# W-BT.net
KiCad netlist of a schematic drawn in EAGLE
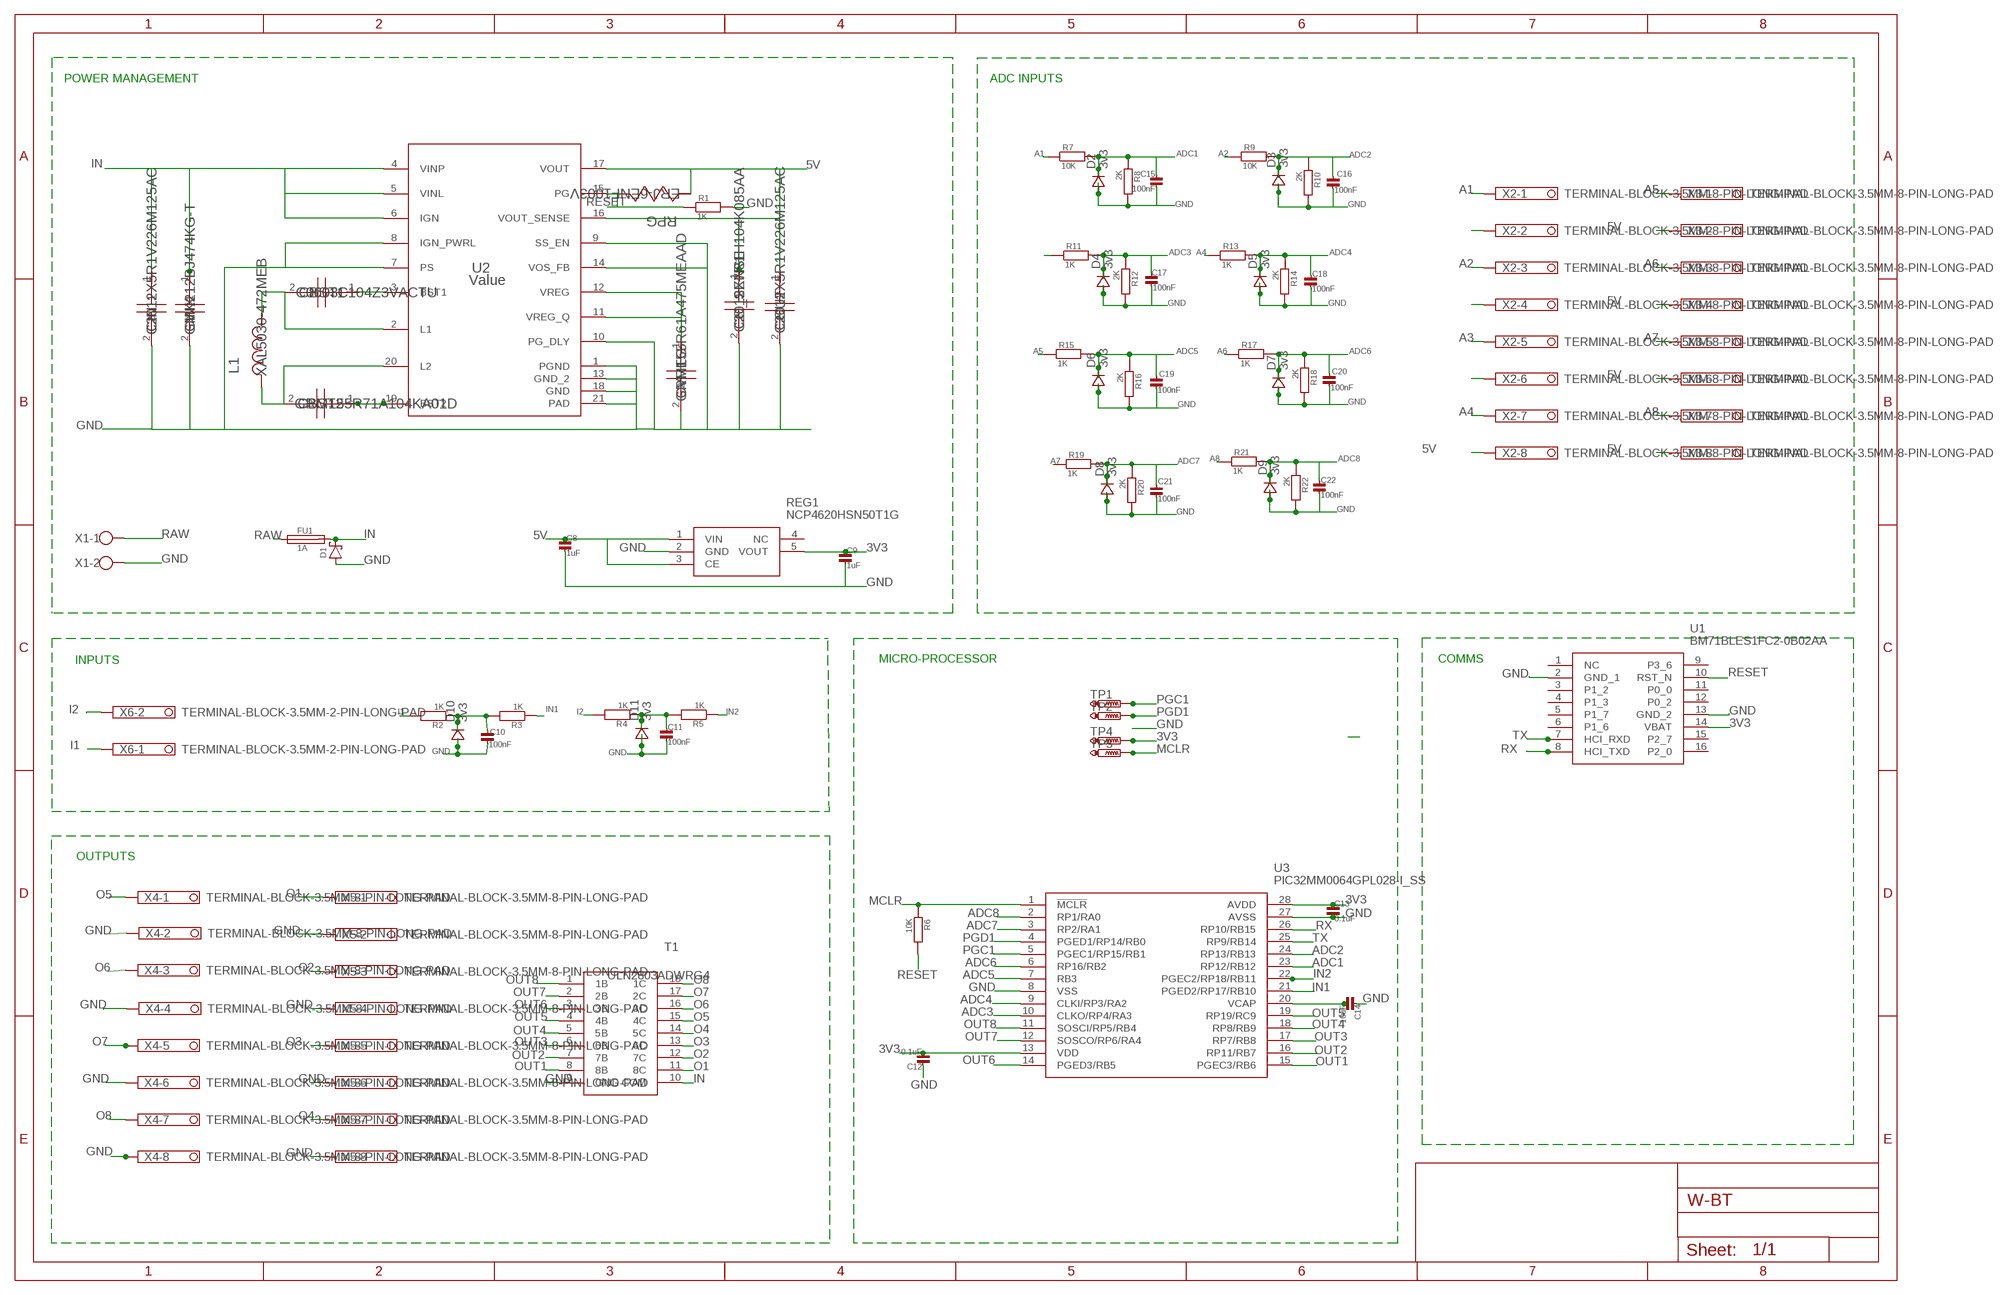
[diagram p0: schematic, sheet 1]

(export (version "E")
  (design (tool "Eeschema 10.0.6"))
  (components
    (comp (ref "C8")
      (value "1uF")
      (footprint "eagle-import:C0402")
      (libsource (lib "eagle-import") (part "CC0402"))
    )
    (comp (ref "C9")
      (value "1uF")
      (footprint "eagle-import:C0402")
      (libsource (lib "eagle-import") (part "CC0402"))
    )
    (comp (ref "C10")
      (value "100nF")
      (footprint "eagle-import:C0402")
      (libsource (lib "eagle-import") (part "CC0402"))
    )
    (comp (ref "C11")
      (value "100nF")
      (footprint "eagle-import:C0402")
      (libsource (lib "eagle-import") (part "CC0402"))
    )
    (comp (ref "C12")
      (value "0.1uF")
      (footprint "eagle-import:C0402")
      (libsource (lib "eagle-import") (part "CC0402"))
    )
    (comp (ref "C13")
      (value "0.1uF")
      (footprint "eagle-import:C0402")
      (libsource (lib "eagle-import") (part "CC0402"))
    )
    (comp (ref "C14")
      (value "10uF")
      (footprint "eagle-import:C0402")
      (libsource (lib "eagle-import") (part "CC0402"))
    )
    (comp (ref "C15")
      (value "100nF")
      (footprint "eagle-import:C0402")
      (libsource (lib "eagle-import") (part "CC0402"))
    )
    (comp (ref "C16")
      (value "100nF")
      (footprint "eagle-import:C0402")
      (libsource (lib "eagle-import") (part "CC0402"))
    )
    (comp (ref "C17")
      (value "100nF")
      (footprint "eagle-import:C0402")
      (libsource (lib "eagle-import") (part "CC0402"))
    )
    (comp (ref "C18")
      (value "100nF")
      (footprint "eagle-import:C0402")
      (libsource (lib "eagle-import") (part "CC0402"))
    )
    (comp (ref "C19")
      (value "100nF")
      (footprint "eagle-import:C0402")
      (libsource (lib "eagle-import") (part "CC0402"))
    )
    (comp (ref "C20")
      (value "100nF")
      (footprint "eagle-import:C0402")
      (libsource (lib "eagle-import") (part "CC0402"))
    )
    (comp (ref "C21")
      (value "100nF")
      (footprint "eagle-import:C0402")
      (libsource (lib "eagle-import") (part "CC0402"))
    )
    (comp (ref "C22")
      (value "100nF")
      (footprint "eagle-import:C0402")
      (libsource (lib "eagle-import") (part "CC0402"))
    )
    (comp (ref "CBST1")
      (value "C0603C104Z3VACTU")
      (footprint "eagle-import:0603")
      (libsource (lib "eagle-import") (part "C0603C104Z3VACTU"))
    )
    (comp (ref "CBST2")
      (value "GRM155R71A104KA01D")
      (footprint "eagle-import:0402")
      (libsource (lib "eagle-import") (part "GRM155R71A104KA01D"))
    )
    (comp (ref "CIN")
      (value "C2012X5R1V226M125AC")
      (footprint "eagle-import:0805")
      (libsource (lib "eagle-import") (part "C2012X5R1V226M125AC"))
    )
    (comp (ref "CINX")
      (value "GMK212BJ474KG-T")
      (footprint "eagle-import:0805")
      (fields (field (name "MANUFACTURER_PART_NUMBER") "GMK212BJ474KGT"))
      (libsource (lib "eagle-import") (part "GMK212BJ474KG-T"))
    )
    (comp (ref "COUT")
      (value "C2012X5R1V226M125AC")
      (footprint "eagle-import:0805")
      (libsource (lib "eagle-import") (part "C2012X5R1V226M125AC"))
    )
    (comp (ref "CO_SENSE")
      (value "C2012X7R1H104K085AA")
      (footprint "eagle-import:0805")
      (libsource (lib "eagle-import") (part "C2012X7R1H104K085AA"))
    )
    (comp (ref "CVREG")
      (value "GRM155R61A475MEAAD")
      (footprint "eagle-import:0402")
      (libsource (lib "eagle-import") (part "GRM155R61A475MEAAD"))
    )
    (comp (ref "D1")
      (value "SCHOTTKY-DIODESMD")
      (footprint "eagle-import:SMB")
      (libsource (lib "eagle-import") (part "SCHOTTKY-DIODESMD"))
    )
    (comp (ref "D2")
      (value "3v3")
      (footprint "eagle-import:SOD323")
      (fields (field (name "MPN") "CDSOD323-T05C"))
      (libsource (lib "eagle-import") (part "DSOD323"))
    )
    (comp (ref "D3")
      (value "3v3")
      (footprint "eagle-import:SOD323")
      (fields (field (name "MPN") "CDSOD323-T05C"))
      (libsource (lib "eagle-import") (part "DSOD323"))
    )
    (comp (ref "D4")
      (value "3v3")
      (footprint "eagle-import:SOD323")
      (fields (field (name "MPN") "CDSOD323-T05C"))
      (libsource (lib "eagle-import") (part "DSOD323"))
    )
    (comp (ref "D5")
      (value "3v3")
      (footprint "eagle-import:SOD323")
      (fields (field (name "MPN") "CDSOD323-T05C"))
      (libsource (lib "eagle-import") (part "DSOD323"))
    )
    (comp (ref "D6")
      (value "3v3")
      (footprint "eagle-import:SOD323")
      (fields (field (name "MPN") "CDSOD323-T05C"))
      (libsource (lib "eagle-import") (part "DSOD323"))
    )
    (comp (ref "D7")
      (value "3v3")
      (footprint "eagle-import:SOD323")
      (fields (field (name "MPN") "CDSOD323-T05C"))
      (libsource (lib "eagle-import") (part "DSOD323"))
    )
    (comp (ref "D8")
      (value "3v3")
      (footprint "eagle-import:SOD323")
      (fields (field (name "MPN") "CDSOD323-T05C"))
      (libsource (lib "eagle-import") (part "DSOD323"))
    )
    (comp (ref "D9")
      (value "3v3")
      (footprint "eagle-import:SOD323")
      (fields (field (name "MPN") "CDSOD323-T05C"))
      (libsource (lib "eagle-import") (part "DSOD323"))
    )
    (comp (ref "D10")
      (value "3v3")
      (footprint "eagle-import:SOD323")
      (fields (field (name "MPN") "CDSOD323-T05C"))
      (libsource (lib "eagle-import") (part "DSOD323"))
    )
    (comp (ref "D11")
      (value "3v3")
      (footprint "eagle-import:SOD323")
      (fields (field (name "MPN") "CDSOD323-T05C"))
      (libsource (lib "eagle-import") (part "DSOD323"))
    )
    (comp (ref "FU1")
      (value "1A")
      (footprint "eagle-import:MF-SMDF050")
      (libsource (lib "eagle-import") (part "MF-SMDF050"))
    )
    (comp (ref "L1")
      (value "XAL5030-472MEB")
      (footprint "eagle-import:XAL5030")
      (fields (field (name "MANUFACTURER_PART_NUMBER") "XAL5030472MEB"))
      (libsource (lib "eagle-import") (part "XAL5030-472MEB"))
    )
    (comp (ref "R1")
      (value "1K")
      (footprint "eagle-import:R0402")
      (libsource (lib "eagle-import") (part "RR0402"))
    )
    (comp (ref "R2")
      (value "1K")
      (footprint "eagle-import:R0402")
      (libsource (lib "eagle-import") (part "RR0402"))
    )
    (comp (ref "R3")
      (value "1K")
      (footprint "eagle-import:R0402")
      (libsource (lib "eagle-import") (part "RR0402"))
    )
    (comp (ref "R4")
      (value "1K")
      (footprint "eagle-import:R0402")
      (libsource (lib "eagle-import") (part "RR0402"))
    )
    (comp (ref "R5")
      (value "1K")
      (footprint "eagle-import:R0402")
      (libsource (lib "eagle-import") (part "RR0402"))
    )
    (comp (ref "R6")
      (value "10K")
      (footprint "eagle-import:R0402")
      (libsource (lib "eagle-import") (part "RR0402"))
    )
    (comp (ref "R7")
      (value "10K")
      (footprint "eagle-import:R0402")
      (libsource (lib "eagle-import") (part "RR0402"))
    )
    (comp (ref "R8")
      (value "2K")
      (footprint "eagle-import:R0402")
      (libsource (lib "eagle-import") (part "RR0402"))
    )
    (comp (ref "R9")
      (value "10K")
      (footprint "eagle-import:R0402")
      (libsource (lib "eagle-import") (part "RR0402"))
    )
    (comp (ref "R10")
      (value "2K")
      (footprint "eagle-import:R0402")
      (libsource (lib "eagle-import") (part "RR0402"))
    )
    (comp (ref "R11")
      (value "1K")
      (footprint "eagle-import:R0402")
      (libsource (lib "eagle-import") (part "RR0402"))
    )
    (comp (ref "R12")
      (value "2K")
      (footprint "eagle-import:R0402")
      (libsource (lib "eagle-import") (part "RR0402"))
    )
    (comp (ref "R13")
      (value "1K")
      (footprint "eagle-import:R0402")
      (libsource (lib "eagle-import") (part "RR0402"))
    )
    (comp (ref "R14")
      (value "2K")
      (footprint "eagle-import:R0402")
      (libsource (lib "eagle-import") (part "RR0402"))
    )
    (comp (ref "R15")
      (value "1K")
      (footprint "eagle-import:R0402")
      (libsource (lib "eagle-import") (part "RR0402"))
    )
    (comp (ref "R16")
      (value "2K")
      (footprint "eagle-import:R0402")
      (libsource (lib "eagle-import") (part "RR0402"))
    )
    (comp (ref "R17")
      (value "1K")
      (footprint "eagle-import:R0402")
      (libsource (lib "eagle-import") (part "RR0402"))
    )
    (comp (ref "R18")
      (value "2K")
      (footprint "eagle-import:R0402")
      (libsource (lib "eagle-import") (part "RR0402"))
    )
    (comp (ref "R19")
      (value "1K")
      (footprint "eagle-import:R0402")
      (libsource (lib "eagle-import") (part "RR0402"))
    )
    (comp (ref "R20")
      (value "2K")
      (footprint "eagle-import:R0402")
      (libsource (lib "eagle-import") (part "RR0402"))
    )
    (comp (ref "R21")
      (value "1K")
      (footprint "eagle-import:R0402")
      (libsource (lib "eagle-import") (part "RR0402"))
    )
    (comp (ref "R22")
      (value "2K")
      (footprint "eagle-import:R0402")
      (libsource (lib "eagle-import") (part "RR0402"))
    )
    (comp (ref "REG1")
      (value "NCP4620HSN50T1G")
      (footprint "eagle-import:SOT95P280X145-5N")
      (fields
        (field (name "MOUSER_PART_NUMBER") "863-NCP4620HSN50T1G")
        (field (name "RS_PART_NUMBER") "7484802")
      )
      (libsource (lib "eagle-import") (part "NCP4620HSN50T1G"))
    )
    (comp (ref "RPG")
      (value "ERJ-6ENF1003V")
      (footprint "eagle-import:0805")
      (fields
        (field (name "MANUFACTURER_PART_NUMBER") "ERJ6ENF1003V")
        (field (name "POWER") "0.125")
        (field (name "TOLERANCE") "1.0")
      )
      (libsource (lib "eagle-import") (part "ERJ-6ENF1003V"))
    )
    (comp (ref "T1")
      (value "ULN2803ADWRG4")
      (footprint "eagle-import:SOIC127P1030X265-18N")
      (fields (field (name "MOUSER_PART_NUMBER") "595-ULN2803ADWRG4"))
      (libsource (lib "eagle-import") (part "ULN2803ADWRG4"))
    )
    (comp (ref "TP1")
      (value "PTR1TP13R")
      (footprint "eagle-import:TP13R")
      (libsource (lib "eagle-import") (part "PTR1TP13R"))
    )
    (comp (ref "TP2")
      (value "PTR1TP13R")
      (footprint "eagle-import:TP13R")
      (libsource (lib "eagle-import") (part "PTR1TP13R"))
    )
    (comp (ref "TP4")
      (value "PTR1TP13R")
      (footprint "eagle-import:TP13R")
      (libsource (lib "eagle-import") (part "PTR1TP13R"))
    )
    (comp (ref "TP5")
      (value "PTR1TP13SQ")
      (footprint "eagle-import:TP13SQ")
      (libsource (lib "eagle-import") (part "PTR1TP13SQ"))
    )
    (comp (ref "U1")
      (value "BM71BLES1FC2-0B02AA")
      (footprint "eagle-import:BM71BLES1FC2_1")
      (fields
        (field (name "MOUSER_PART_NUMBER") "579-71BLES1FC20B02AA")
        (field (name "RS_PART_NUMBER") "1717856P")
      )
      (libsource (lib "eagle-import") (part "BM71BLES1FC2-0B02AA"))
    )
    (comp (ref "U2")
      (value "Value")
      (footprint "eagle-import:PWP0020P_N")
      (fields
        (field (name "MANUFACTURER") "Texas Instruments")
        (field (name "MANUFACTURER_PART_NUMBER") "TPS55165QPWPRQ1")
        (field (name "PARTNUMBER") "TPS55165PWPQ1")
      )
      (libsource (lib "eagle-import") (part "TPS55165QPWPRQ1"))
    )
    (comp (ref "U3")
      (value "PIC32MM0064GPL028-I_SS")
      (footprint "eagle-import:SOP65P780X200-28N")
      (fields
        (field (name "MANUFACTURER_PART_NUMBER") "PIC32MM0064GPL028-I/SS")
        (field (name "MOUSER_PART_NUMBER") "579-2MM0064GPL028ISS")
        (field (name "RS_PART_NUMBER") "1463267")
      )
      (libsource (lib "eagle-import") (part "PIC32MM0064GPL028-I_SS"))
    )
    (comp (ref "X1")
      (value "W237-102")
      (footprint "eagle-import:W237-102")
      (fields (field (name "MPN") "237-102"))
      (libsource (lib "eagle-import") (part "W237-102"))
    )
    (comp (ref "X2")
      (value "TERMINAL-BLOCK-3.5MM-8-PIN-LONG-PAD")
      (footprint "eagle-import:TERMINAL-BLOCK-8-PIN-3.5MM-LONG-PAD")
      (libsource (lib "eagle-import") (part "TERMINAL-BLOCK-3.5MM-8-PIN-LONG-PAD"))
    )
    (comp (ref "X3")
      (value "TERMINAL-BLOCK-3.5MM-8-PIN-LONG-PAD")
      (footprint "eagle-import:TERMINAL-BLOCK-8-PIN-3.5MM-LONG-PAD")
      (libsource (lib "eagle-import") (part "TERMINAL-BLOCK-3.5MM-8-PIN-LONG-PAD"))
    )
    (comp (ref "X4")
      (value "TERMINAL-BLOCK-3.5MM-8-PIN-LONG-PAD")
      (footprint "eagle-import:TERMINAL-BLOCK-8-PIN-3.5MM-LONG-PAD")
      (libsource (lib "eagle-import") (part "TERMINAL-BLOCK-3.5MM-8-PIN-LONG-PAD"))
    )
    (comp (ref "X5")
      (value "TERMINAL-BLOCK-3.5MM-8-PIN-LONG-PAD")
      (footprint "eagle-import:TERMINAL-BLOCK-8-PIN-3.5MM-LONG-PAD")
      (libsource (lib "eagle-import") (part "TERMINAL-BLOCK-3.5MM-8-PIN-LONG-PAD"))
    )
    (comp (ref "X6")
      (value "TERMINAL-BLOCK-3.5MM-2-PIN-LONG-PAD")
      (footprint "eagle-import:TERMINAL-BLOCK-2-PIN-3.5MM-LONG-PAD")
      (libsource (lib "eagle-import") (part "TERMINAL-BLOCK-3.5MM-2-PIN-LONG-PAD"))
    )
  )
  (nets
    (net (code "1") (name "/3V3") (class "Default")
      (node (ref "C12") (pin "2") (pinfunction "2_2") (pintype "passive"))
      (node (ref "C13") (pin "1") (pinfunction "1_1") (pintype "passive"))
      (node (ref "C9") (pin "1") (pinfunction "1_1") (pintype "passive"))
      (node (ref "REG1") (pin "5") (pinfunction "VOUT_5") (pintype "output"))
      (node (ref "TP4") (pin "TP") (pinfunction "TP_TP") (pintype "input"))
      (node (ref "U1") (pin "14") (pinfunction "VBAT_14") (pintype "bidirectional"))
      (node (ref "U3") (pin "13") (pinfunction "VDD_13") (pintype "bidirectional"))
      (node (ref "U3") (pin "28") (pinfunction "AVDD_28") (pintype "bidirectional"))
    )
    (net (code "2") (name "/5V") (class "Default")
      (node (ref "C8") (pin "1") (pinfunction "1_1") (pintype "passive"))
      (node (ref "COUT") (pin "1") (pinfunction "1_1") (pintype "passive"))
      (node (ref "CO_SENSE") (pin "1") (pinfunction "1_1") (pintype "passive"))
      (node (ref "REG1") (pin "1") (pinfunction "VIN_1") (pintype "input"))
      (node (ref "REG1") (pin "3") (pinfunction "CE_3") (pintype "bidirectional"))
      (node (ref "RPG") (pin "2") (pinfunction "2_2") (pintype "passive"))
      (node (ref "U2") (pin "16") (pinfunction "VOUT_SENSE_16") (pintype "input"))
      (node (ref "U2") (pin "17") (pinfunction "VOUT_17") (pintype "power_in"))
      (node (ref "X2") (pin "2") (pinfunction "K_2") (pintype "passive"))
      (node (ref "X2") (pin "4") (pinfunction "K_4") (pintype "passive"))
      (node (ref "X2") (pin "6") (pinfunction "K_6") (pintype "passive"))
      (node (ref "X2") (pin "8") (pinfunction "K_8") (pintype "passive"))
      (node (ref "X3") (pin "2") (pinfunction "K_2") (pintype "passive"))
      (node (ref "X3") (pin "4") (pinfunction "K_4") (pintype "passive"))
      (node (ref "X3") (pin "6") (pinfunction "K_6") (pintype "passive"))
      (node (ref "X3") (pin "8") (pinfunction "K_8") (pintype "passive"))
    )
    (net (code "3") (name "/A1") (class "Default")
      (node (ref "R7") (pin "1") (pinfunction "1_1") (pintype "passive"))
      (node (ref "X2") (pin "1") (pinfunction "K_1") (pintype "passive"))
    )
    (net (code "4") (name "/A2") (class "Default")
      (node (ref "R9") (pin "1") (pinfunction "1_1") (pintype "passive"))
      (node (ref "X2") (pin "3") (pinfunction "K_3") (pintype "passive"))
    )
    (net (code "5") (name "/A3") (class "Default")
      (node (ref "R11") (pin "1") (pinfunction "1_1") (pintype "passive"))
      (node (ref "X2") (pin "5") (pinfunction "K_5") (pintype "passive"))
    )
    (net (code "6") (name "/A4") (class "Default")
      (node (ref "R13") (pin "1") (pinfunction "1_1") (pintype "passive"))
      (node (ref "X2") (pin "7") (pinfunction "K_7") (pintype "passive"))
    )
    (net (code "7") (name "/A5") (class "Default")
      (node (ref "R15") (pin "1") (pinfunction "1_1") (pintype "passive"))
      (node (ref "X3") (pin "1") (pinfunction "K_1") (pintype "passive"))
    )
    (net (code "8") (name "/A6") (class "Default")
      (node (ref "R17") (pin "1") (pinfunction "1_1") (pintype "passive"))
      (node (ref "X3") (pin "3") (pinfunction "K_3") (pintype "passive"))
    )
    (net (code "9") (name "/A7") (class "Default")
      (node (ref "R19") (pin "1") (pinfunction "1_1") (pintype "passive"))
      (node (ref "X3") (pin "5") (pinfunction "K_5") (pintype "passive"))
    )
    (net (code "10") (name "/A8") (class "Default")
      (node (ref "R21") (pin "1") (pinfunction "1_1") (pintype "passive"))
      (node (ref "X3") (pin "7") (pinfunction "K_7") (pintype "passive"))
    )
    (net (code "11") (name "/ADC1") (class "Default")
      (node (ref "C15") (pin "1") (pinfunction "1_1") (pintype "passive"))
      (node (ref "D2") (pin "1") (pinfunction "C_1") (pintype "passive"))
      (node (ref "R7") (pin "2") (pinfunction "2_2") (pintype "passive"))
      (node (ref "R8") (pin "1") (pinfunction "1_1") (pintype "passive"))
      (node (ref "U3") (pin "23") (pinfunction "RP12/RB12_23") (pintype "bidirectional"))
    )
    (net (code "12") (name "/ADC2") (class "Default")
      (node (ref "C16") (pin "1") (pinfunction "1_1") (pintype "passive"))
      (node (ref "D3") (pin "1") (pinfunction "C_1") (pintype "passive"))
      (node (ref "R10") (pin "1") (pinfunction "1_1") (pintype "passive"))
      (node (ref "R9") (pin "2") (pinfunction "2_2") (pintype "passive"))
      (node (ref "U3") (pin "24") (pinfunction "RP13/RB13_24") (pintype "bidirectional"))
    )
    (net (code "13") (name "/ADC3") (class "Default")
      (node (ref "C17") (pin "1") (pinfunction "1_1") (pintype "passive"))
      (node (ref "D4") (pin "1") (pinfunction "C_1") (pintype "passive"))
      (node (ref "R11") (pin "2") (pinfunction "2_2") (pintype "passive"))
      (node (ref "R12") (pin "1") (pinfunction "1_1") (pintype "passive"))
      (node (ref "U3") (pin "10") (pinfunction "CLKO/RP4/RA3_10") (pintype "bidirectional"))
    )
    (net (code "14") (name "/ADC4") (class "Default")
      (node (ref "C18") (pin "1") (pinfunction "1_1") (pintype "passive"))
      (node (ref "D5") (pin "1") (pinfunction "C_1") (pintype "passive"))
      (node (ref "R13") (pin "2") (pinfunction "2_2") (pintype "passive"))
      (node (ref "R14") (pin "1") (pinfunction "1_1") (pintype "passive"))
      (node (ref "U3") (pin "9") (pinfunction "CLKI/RP3/RA2_9") (pintype "bidirectional"))
    )
    (net (code "15") (name "/ADC5") (class "Default")
      (node (ref "C19") (pin "1") (pinfunction "1_1") (pintype "passive"))
      (node (ref "D6") (pin "1") (pinfunction "C_1") (pintype "passive"))
      (node (ref "R15") (pin "2") (pinfunction "2_2") (pintype "passive"))
      (node (ref "R16") (pin "1") (pinfunction "1_1") (pintype "passive"))
      (node (ref "U3") (pin "7") (pinfunction "RB3_7") (pintype "bidirectional"))
    )
    (net (code "16") (name "/ADC6") (class "Default")
      (node (ref "C20") (pin "1") (pinfunction "1_1") (pintype "passive"))
      (node (ref "D7") (pin "1") (pinfunction "C_1") (pintype "passive"))
      (node (ref "R17") (pin "2") (pinfunction "2_2") (pintype "passive"))
      (node (ref "R18") (pin "1") (pinfunction "1_1") (pintype "passive"))
      (node (ref "U3") (pin "6") (pinfunction "RP16/RB2_6") (pintype "bidirectional"))
    )
    (net (code "17") (name "/ADC7") (class "Default")
      (node (ref "C21") (pin "1") (pinfunction "1_1") (pintype "passive"))
      (node (ref "D8") (pin "1") (pinfunction "C_1") (pintype "passive"))
      (node (ref "R19") (pin "2") (pinfunction "2_2") (pintype "passive"))
      (node (ref "R20") (pin "1") (pinfunction "1_1") (pintype "passive"))
      (node (ref "U3") (pin "3") (pinfunction "RP2/RA1_3") (pintype "bidirectional"))
    )
    (net (code "18") (name "/ADC8") (class "Default")
      (node (ref "C22") (pin "1") (pinfunction "1_1") (pintype "passive"))
      (node (ref "D9") (pin "1") (pinfunction "C_1") (pintype "passive"))
      (node (ref "R21") (pin "2") (pinfunction "2_2") (pintype "passive"))
      (node (ref "R22") (pin "1") (pinfunction "1_1") (pintype "passive"))
      (node (ref "U3") (pin "2") (pinfunction "RP1/RA0_2") (pintype "bidirectional"))
    )
    (net (code "19") (name "/GND") (class "Default")
      (node (ref "C10") (pin "2") (pinfunction "2_2") (pintype "passive"))
      (node (ref "C11") (pin "2") (pinfunction "2_2") (pintype "passive"))
      (node (ref "C12") (pin "1") (pinfunction "1_1") (pintype "passive"))
      (node (ref "C13") (pin "2") (pinfunction "2_2") (pintype "passive"))
      (node (ref "C14") (pin "1") (pinfunction "1_1") (pintype "passive"))
      (node (ref "C15") (pin "2") (pinfunction "2_2") (pintype "passive"))
      (node (ref "C16") (pin "2") (pinfunction "2_2") (pintype "passive"))
      (node (ref "C17") (pin "2") (pinfunction "2_2") (pintype "passive"))
      (node (ref "C18") (pin "2") (pinfunction "2_2") (pintype "passive"))
      (node (ref "C19") (pin "2") (pinfunction "2_2") (pintype "passive"))
      (node (ref "C20") (pin "2") (pinfunction "2_2") (pintype "passive"))
      (node (ref "C21") (pin "2") (pinfunction "2_2") (pintype "passive"))
      (node (ref "C22") (pin "2") (pinfunction "2_2") (pintype "passive"))
      (node (ref "C8") (pin "2") (pinfunction "2_2") (pintype "passive"))
      (node (ref "C9") (pin "2") (pinfunction "2_2") (pintype "passive"))
      (node (ref "CIN") (pin "2") (pinfunction "2_2") (pintype "passive"))
      (node (ref "CINX") (pin "2") (pinfunction "2_2") (pintype "passive"))
      (node (ref "COUT") (pin "2") (pinfunction "2_2") (pintype "passive"))
      (node (ref "CO_SENSE") (pin "2") (pinfunction "2_2") (pintype "passive"))
      (node (ref "CVREG") (pin "2") (pinfunction "2_2") (pintype "passive"))
      (node (ref "D1") (pin "A") (pinfunction "A_A") (pintype "passive"))
      (node (ref "D10") (pin "2") (pinfunction "A_2") (pintype "passive"))
      (node (ref "D11") (pin "2") (pinfunction "A_2") (pintype "passive"))
      (node (ref "D2") (pin "2") (pinfunction "A_2") (pintype "passive"))
      (node (ref "D3") (pin "2") (pinfunction "A_2") (pintype "passive"))
      (node (ref "D4") (pin "2") (pinfunction "A_2") (pintype "passive"))
      (node (ref "D5") (pin "2") (pinfunction "A_2") (pintype "passive"))
      (node (ref "D6") (pin "2") (pinfunction "A_2") (pintype "passive"))
      (node (ref "D7") (pin "2") (pinfunction "A_2") (pintype "passive"))
      (node (ref "D8") (pin "2") (pinfunction "A_2") (pintype "passive"))
      (node (ref "D9") (pin "2") (pinfunction "A_2") (pintype "passive"))
      (node (ref "R1") (pin "2") (pinfunction "2_2") (pintype "passive"))
      (node (ref "R10") (pin "2") (pinfunction "2_2") (pintype "passive"))
      (node (ref "R12") (pin "2") (pinfunction "2_2") (pintype "passive"))
      (node (ref "R14") (pin "2") (pinfunction "2_2") (pintype "passive"))
      (node (ref "R16") (pin "2") (pinfunction "2_2") (pintype "passive"))
      (node (ref "R18") (pin "2") (pinfunction "2_2") (pintype "passive"))
      (node (ref "R20") (pin "2") (pinfunction "2_2") (pintype "passive"))
      (node (ref "R22") (pin "2") (pinfunction "2_2") (pintype "passive"))
      (node (ref "R8") (pin "2") (pinfunction "2_2") (pintype "passive"))
      (node (ref "REG1") (pin "2") (pinfunction "GND_2") (pintype "power_in"))
      (node (ref "T1") (pin "9") (pinfunction "GND_9") (pintype "bidirectional"))
      (node (ref "U1") (pin "13") (pinfunction "GND_2_13") (pintype "bidirectional"))
      (node (ref "U1") (pin "2") (pinfunction "GND_1_2") (pintype "bidirectional"))
      (node (ref "U2") (pin "1") (pinfunction "PGND_1") (pintype "power_in"))
      (node (ref "U2") (pin "10") (pinfunction "PG_DLY_10") (pintype "input"))
      (node (ref "U2") (pin "13") (pinfunction "GND_2_13") (pintype "power_in"))
      (node (ref "U2") (pin "14") (pinfunction "VOS_FB_14") (pintype "input"))
      (node (ref "U2") (pin "18") (pinfunction "GND_18") (pintype "power_in"))
      (node (ref "U2") (pin "21") (pinfunction "PAD_21") (pintype "power_in"))
      (node (ref "U2") (pin "7") (pinfunction "PS_7") (pintype "input"))
      (node (ref "U2") (pin "8") (pinfunction "IGN_PWRL_8") (pintype "input"))
      (node (ref "U2") (pin "9") (pinfunction "SS_EN_9") (pintype "input"))
      (node (ref "U3") (pin "27") (pinfunction "AVSS_27") (pintype "bidirectional"))
      (node (ref "U3") (pin "8") (pinfunction "VSS_8") (pintype "bidirectional"))
      (node (ref "X1") (pin "2") (pinfunction "KL_2") (pintype "passive"))
      (node (ref "X4") (pin "2") (pinfunction "K_2") (pintype "passive"))
      (node (ref "X4") (pin "4") (pinfunction "K_4") (pintype "passive"))
      (node (ref "X4") (pin "6") (pinfunction "K_6") (pintype "passive"))
      (node (ref "X4") (pin "8") (pinfunction "K_8") (pintype "passive"))
      (node (ref "X5") (pin "2") (pinfunction "K_2") (pintype "passive"))
      (node (ref "X5") (pin "4") (pinfunction "K_4") (pintype "passive"))
      (node (ref "X5") (pin "6") (pinfunction "K_6") (pintype "passive"))
      (node (ref "X5") (pin "8") (pinfunction "K_8") (pintype "passive"))
    )
    (net (code "20") (name "/I1") (class "Default")
      (node (ref "R2") (pin "2") (pinfunction "2_2") (pintype "passive"))
      (node (ref "X6") (pin "1") (pinfunction "K_1") (pintype "passive"))
    )
    (net (code "21") (name "/I2") (class "Default")
      (node (ref "R4") (pin "2") (pinfunction "2_2") (pintype "passive"))
      (node (ref "X6") (pin "2") (pinfunction "K_2") (pintype "passive"))
    )
    (net (code "22") (name "/IN") (class "Default")
      (node (ref "CIN") (pin "1") (pinfunction "1_1") (pintype "passive"))
      (node (ref "CINX") (pin "1") (pinfunction "1_1") (pintype "passive"))
      (node (ref "D1") (pin "C") (pinfunction "C_C") (pintype "passive"))
      (node (ref "FU1") (pin "2") (pinfunction "2_2") (pintype "passive"))
      (node (ref "T1") (pin "10") (pinfunction "COM_10") (pintype "bidirectional"))
      (node (ref "U2") (pin "4") (pinfunction "VINP_4") (pintype "power_in"))
      (node (ref "U2") (pin "5") (pinfunction "VINL_5") (pintype "power_in"))
      (node (ref "U2") (pin "6") (pinfunction "IGN_6") (pintype "input"))
    )
    (net (code "23") (name "/IN1") (class "Default")
      (node (ref "R3") (pin "1") (pinfunction "1_1") (pintype "passive"))
      (node (ref "U3") (pin "21") (pinfunction "PGED2/RP17/RB10_21") (pintype "bidirectional"))
    )
    (net (code "24") (name "/IN2") (class "Default")
      (node (ref "R5") (pin "1") (pinfunction "1_1") (pintype "passive"))
      (node (ref "U3") (pin "22") (pinfunction "PGEC2/RP18/RB11_22") (pintype "bidirectional"))
    )
    (net (code "25") (name "/MCLR") (class "Default")
      (node (ref "R6") (pin "1") (pinfunction "1_1") (pintype "passive"))
      (node (ref "TP5") (pin "TP") (pinfunction "TP_TP") (pintype "input"))
      (node (ref "U3") (pin "1") (pinfunction "~{MCLR}_1") (pintype "bidirectional"))
    )
    (net (code "26") (name "/O1") (class "Default")
      (node (ref "T1") (pin "11") (pinfunction "8C_11") (pintype "bidirectional"))
      (node (ref "X5") (pin "1") (pinfunction "K_1") (pintype "passive"))
    )
    (net (code "27") (name "/O2") (class "Default")
      (node (ref "T1") (pin "12") (pinfunction "7C_12") (pintype "bidirectional"))
      (node (ref "X5") (pin "3") (pinfunction "K_3") (pintype "passive"))
    )
    (net (code "28") (name "/O3") (class "Default")
      (node (ref "T1") (pin "13") (pinfunction "6C_13") (pintype "bidirectional"))
      (node (ref "X5") (pin "5") (pinfunction "K_5") (pintype "passive"))
    )
    (net (code "29") (name "/O4") (class "Default")
      (node (ref "T1") (pin "14") (pinfunction "5C_14") (pintype "bidirectional"))
      (node (ref "X5") (pin "7") (pinfunction "K_7") (pintype "passive"))
    )
    (net (code "30") (name "/O5") (class "Default")
      (node (ref "T1") (pin "15") (pinfunction "4C_15") (pintype "bidirectional"))
      (node (ref "X4") (pin "1") (pinfunction "K_1") (pintype "passive"))
    )
    (net (code "31") (name "/O6") (class "Default")
      (node (ref "T1") (pin "16") (pinfunction "3C_16") (pintype "bidirectional"))
      (node (ref "X4") (pin "3") (pinfunction "K_3") (pintype "passive"))
    )
    (net (code "32") (name "/O7") (class "Default")
      (node (ref "T1") (pin "17") (pinfunction "2C_17") (pintype "bidirectional"))
      (node (ref "X4") (pin "5") (pinfunction "K_5") (pintype "passive"))
    )
    (net (code "33") (name "/O8") (class "Default")
      (node (ref "T1") (pin "18") (pinfunction "1C_18") (pintype "bidirectional"))
      (node (ref "X4") (pin "7") (pinfunction "K_7") (pintype "passive"))
    )
    (net (code "34") (name "/OUT1") (class "Default")
      (node (ref "T1") (pin "8") (pinfunction "8B_8") (pintype "bidirectional"))
      (node (ref "U3") (pin "15") (pinfunction "PGEC3/RB6_15") (pintype "bidirectional"))
    )
    (net (code "35") (name "/OUT2") (class "Default")
      (node (ref "T1") (pin "7") (pinfunction "7B_7") (pintype "bidirectional"))
      (node (ref "U3") (pin "16") (pinfunction "RP11/RB7_16") (pintype "bidirectional"))
    )
    (net (code "36") (name "/OUT3") (class "Default")
      (node (ref "T1") (pin "6") (pinfunction "6B_6") (pintype "bidirectional"))
      (node (ref "U3") (pin "17") (pinfunction "RP7/RB8_17") (pintype "bidirectional"))
    )
    (net (code "37") (name "/OUT4") (class "Default")
      (node (ref "T1") (pin "5") (pinfunction "5B_5") (pintype "bidirectional"))
      (node (ref "U3") (pin "18") (pinfunction "RP8/RB9_18") (pintype "bidirectional"))
    )
    (net (code "38") (name "/OUT5") (class "Default")
      (node (ref "T1") (pin "4") (pinfunction "4B_4") (pintype "bidirectional"))
      (node (ref "U3") (pin "19") (pinfunction "RP19/RC9_19") (pintype "bidirectional"))
    )
    (net (code "39") (name "/OUT6") (class "Default")
      (node (ref "T1") (pin "3") (pinfunction "3B_3") (pintype "bidirectional"))
      (node (ref "U3") (pin "14") (pinfunction "PGED3/RB5_14") (pintype "bidirectional"))
    )
    (net (code "40") (name "/OUT7") (class "Default")
      (node (ref "T1") (pin "2") (pinfunction "2B_2") (pintype "bidirectional"))
      (node (ref "U3") (pin "12") (pinfunction "SOSCO/RP6/RA4_12") (pintype "bidirectional"))
    )
    (net (code "41") (name "/OUT8") (class "Default")
      (node (ref "T1") (pin "1") (pinfunction "1B_1") (pintype "bidirectional"))
      (node (ref "U3") (pin "11") (pinfunction "SOSCI/RP5/RB4_11") (pintype "bidirectional"))
    )
    (net (code "42") (name "/PGC1") (class "Default")
      (node (ref "TP1") (pin "TP") (pinfunction "TP_TP") (pintype "input"))
      (node (ref "U3") (pin "5") (pinfunction "PGEC1/RP15/RB1_5") (pintype "bidirectional"))
    )
    (net (code "43") (name "/PGD1") (class "Default")
      (node (ref "TP2") (pin "TP") (pinfunction "TP_TP") (pintype "input"))
      (node (ref "U3") (pin "4") (pinfunction "PGED1/RP14/RB0_4") (pintype "bidirectional"))
    )
    (net (code "44") (name "/RAW") (class "Default")
      (node (ref "FU1") (pin "1") (pinfunction "1_1") (pintype "passive"))
      (node (ref "X1") (pin "1") (pinfunction "KL_1") (pintype "passive"))
    )
    (net (code "45") (name "/RESET") (class "Default")
      (node (ref "R1") (pin "1") (pinfunction "1_1") (pintype "passive"))
      (node (ref "R6") (pin "2") (pinfunction "2_2") (pintype "passive"))
      (node (ref "RPG") (pin "1") (pinfunction "1_1") (pintype "passive"))
      (node (ref "U1") (pin "10") (pinfunction "RST_N_10") (pintype "bidirectional"))
      (node (ref "U2") (pin "15") (pinfunction "PG_15") (pintype "open_collector"))
    )
    (net (code "46") (name "/RX") (class "Default")
      (node (ref "U1") (pin "8") (pinfunction "HCI_TXD_8") (pintype "bidirectional"))
      (node (ref "U3") (pin "26") (pinfunction "RP10/RB15_26") (pintype "bidirectional"))
    )
    (net (code "47") (name "/TX") (class "Default")
      (node (ref "U1") (pin "7") (pinfunction "HCI_RXD_7") (pintype "bidirectional"))
      (node (ref "U3") (pin "25") (pinfunction "RP9/RB14_25") (pintype "bidirectional"))
    )
    (net (code "48") (name "Net-(D10-C)") (class "Default")
      (node (ref "C10") (pin "1") (pinfunction "1_1") (pintype "passive"))
      (node (ref "D10") (pin "1") (pinfunction "C_1") (pintype "passive"))
      (node (ref "R2") (pin "1") (pinfunction "1_1") (pintype "passive"))
      (node (ref "R3") (pin "2") (pinfunction "2_2") (pintype "passive"))
    )
    (net (code "49") (name "Net-(D11-C)") (class "Default")
      (node (ref "C11") (pin "1") (pinfunction "1_1") (pintype "passive"))
      (node (ref "D11") (pin "1") (pinfunction "C_1") (pintype "passive"))
      (node (ref "R4") (pin "1") (pinfunction "1_1") (pintype "passive"))
      (node (ref "R5") (pin "2") (pinfunction "2_2") (pintype "passive"))
    )
    (net (code "50") (name "Net-(U2-BST1)") (class "Default")
      (node (ref "CBST1") (pin "1") (pinfunction "1_1") (pintype "passive"))
      (node (ref "U2") (pin "3") (pinfunction "BST1_3") (pintype "passive"))
    )
    (net (code "51") (name "Net-(U2-BST2)") (class "Default")
      (node (ref "CBST2") (pin "1") (pinfunction "1_1") (pintype "passive"))
      (node (ref "U2") (pin "19") (pinfunction "BST2_19") (pintype "passive"))
    )
    (net (code "52") (name "Net-(U2-L1)") (class "Default")
      (node (ref "CBST1") (pin "2") (pinfunction "2_2") (pintype "passive"))
      (node (ref "L1") (pin "2") (pinfunction "2_2") (pintype "passive"))
      (node (ref "U2") (pin "2") (pinfunction "L1_2") (pintype "passive"))
    )
    (net (code "53") (name "Net-(U2-L2)") (class "Default")
      (node (ref "CBST2") (pin "2") (pinfunction "2_2") (pintype "passive"))
      (node (ref "L1") (pin "1") (pinfunction "1_1") (pintype "passive"))
      (node (ref "U2") (pin "20") (pinfunction "L2_20") (pintype "passive"))
    )
    (net (code "54") (name "Net-(U2-VREG)") (class "Default")
      (node (ref "CVREG") (pin "1") (pinfunction "1_1") (pintype "passive"))
      (node (ref "U2") (pin "11") (pinfunction "VREG_Q_11") (pintype "input"))
      (node (ref "U2") (pin "12") (pinfunction "VREG_12") (pintype "output"))
    )
    (net (code "55") (name "Net-(U3-VCAP)") (class "Default")
      (node (ref "C14") (pin "2") (pinfunction "2_2") (pintype "passive"))
      (node (ref "U3") (pin "20") (pinfunction "VCAP_20") (pintype "bidirectional"))
    )
    (net (code "56") (name "unconnected-(REG1-NC-Pad4)") (class "Default")
      (node (ref "REG1") (pin "4") (pinfunction "NC_4") (pintype "no_connect"))
    )
    (net (code "57") (name "unconnected-(U1-NC-Pad1)") (class "Default")
      (node (ref "U1") (pin "1") (pinfunction "NC_1") (pintype "no_connect"))
    )
    (net (code "58") (name "unconnected-(U1-P0_0-Pad11)") (class "Default")
      (node (ref "U1") (pin "11") (pinfunction "P0_0_11") (pintype "bidirectional"))
    )
    (net (code "59") (name "unconnected-(U1-P0_2-Pad12)") (class "Default")
      (node (ref "U1") (pin "12") (pinfunction "P0_2_12") (pintype "bidirectional"))
    )
    (net (code "60") (name "unconnected-(U1-P1_2-Pad3)") (class "Default")
      (node (ref "U1") (pin "3") (pinfunction "P1_2_3") (pintype "bidirectional"))
    )
    (net (code "61") (name "unconnected-(U1-P1_3-Pad4)") (class "Default")
      (node (ref "U1") (pin "4") (pinfunction "P1_3_4") (pintype "bidirectional"))
    )
    (net (code "62") (name "unconnected-(U1-P1_6-Pad6)") (class "Default")
      (node (ref "U1") (pin "6") (pinfunction "P1_6_6") (pintype "bidirectional"))
    )
    (net (code "63") (name "unconnected-(U1-P1_7-Pad5)") (class "Default")
      (node (ref "U1") (pin "5") (pinfunction "P1_7_5") (pintype "bidirectional"))
    )
    (net (code "64") (name "unconnected-(U1-P2_0-Pad16)") (class "Default")
      (node (ref "U1") (pin "16") (pinfunction "P2_0_16") (pintype "bidirectional"))
    )
    (net (code "65") (name "unconnected-(U1-P2_7-Pad15)") (class "Default")
      (node (ref "U1") (pin "15") (pinfunction "P2_7_15") (pintype "bidirectional"))
    )
    (net (code "66") (name "unconnected-(U1-P3_6-Pad9)") (class "Default")
      (node (ref "U1") (pin "9") (pinfunction "P3_6_9") (pintype "bidirectional"))
    )
  )
)
